# GPSDO_Supply.net
KiCad netlist of a schematic drawn in Altium Designer
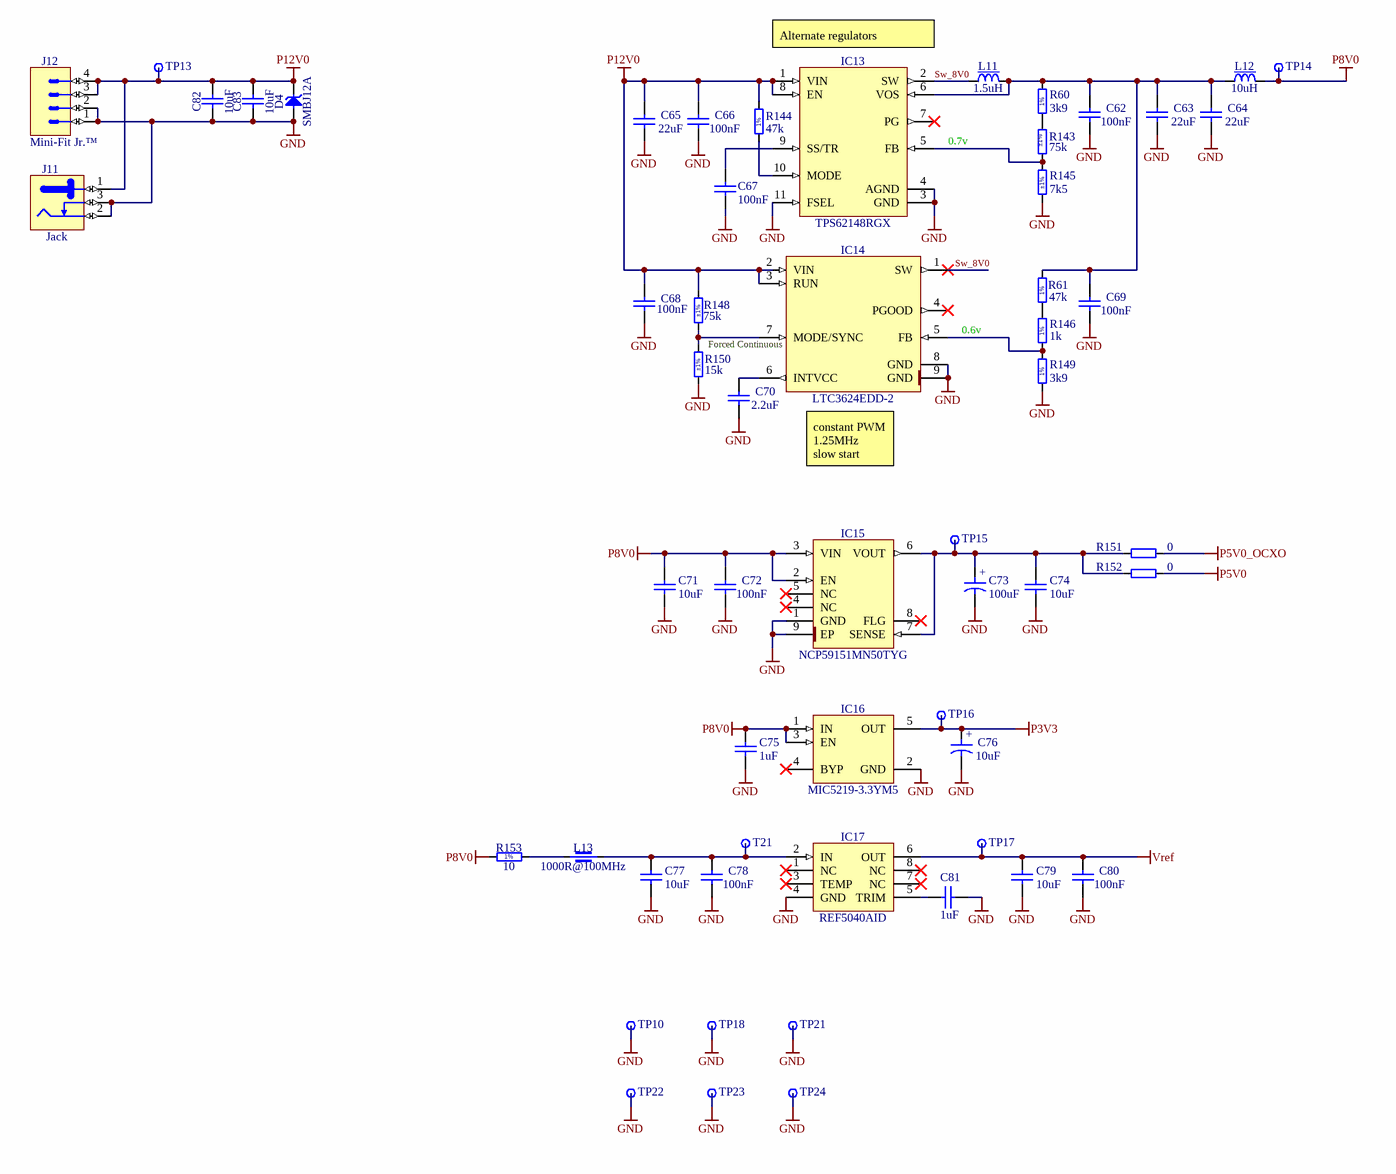
[diagram p0: GPSDO_Supply.SchDoc]

(export (version "E")
  (design (tool "Eeschema 10.0.6"))
  (components
    (comp (ref "C62")
      (value "100nF")
      (footprint "CAPC1005X55N")
      (description "Non-polarised capacitor")
      (fields
        (field (name "PART NUMBER") "CC0402_100NF_16V_10%_X5R")
        (field (name "VOLTAGE") "16V")
        (field (name "AUTHOR") "CERN DEM JLC")
      )
      (libsource (lib "Capacitors") (part "Capacitor - non polarized"))
    )
    (comp (ref "C63")
      (value "22uF")
      (footprint "CAPC2012X135N")
      (description "Non-polarised capacitor")
      (fields
        (field (name "PART NUMBER") "CC0805_22UF_16V_10%_X5R")
        (field (name "VOLTAGE") "16V")
        (field (name "AUTHOR") "CERN DEM JLC")
      )
      (libsource (lib "Capacitors") (part "Capacitor - non polarized"))
    )
    (comp (ref "C64")
      (value "22uF")
      (footprint "CAPC2012X135N")
      (description "Non-polarised capacitor")
      (fields
        (field (name "PART NUMBER") "CC0805_22UF_16V_10%_X5R")
        (field (name "VOLTAGE") "16V")
        (field (name "AUTHOR") "CERN DEM JLC")
      )
      (libsource (lib "Capacitors") (part "Capacitor - non polarized"))
    )
    (comp (ref "C65")
      (value "22uF")
      (footprint "CAPC2012X135N")
      (description "Non-polarised capacitor")
      (fields
        (field (name "PART NUMBER") "CC0805_22UF_16V_10%_X5R")
        (field (name "VOLTAGE") "16V")
        (field (name "AUTHOR") "CERN DEM JLC")
      )
      (libsource (lib "Capacitors") (part "Capacitor - non polarized"))
    )
    (comp (ref "C66")
      (value "100nF")
      (footprint "CAPC1005X55N")
      (description "Non-polarised capacitor")
      (fields
        (field (name "PART NUMBER") "CC0402_100NF_16V_10%_X5R")
        (field (name "VOLTAGE") "16V")
        (field (name "AUTHOR") "CERN DEM JLC")
      )
      (libsource (lib "Capacitors") (part "Capacitor - non polarized"))
    )
    (comp (ref "C67")
      (value "100nF")
      (footprint "CAPC1005X55N")
      (description "Non-polarised capacitor")
      (fields
        (field (name "PART NUMBER") "CC0402_100NF_16V_10%_X5R")
        (field (name "VOLTAGE") "16V")
        (field (name "AUTHOR") "CERN DEM JLC")
      )
      (libsource (lib "Capacitors") (part "Capacitor - non polarized"))
    )
    (comp (ref "C68")
      (value "100nF")
      (footprint "CAPC1005X55N")
      (description "Non-polarised capacitor")
      (fields
        (field (name "PART NUMBER") "CC0402_100NF_16V_10%_X5R")
        (field (name "VOLTAGE") "16V")
        (field (name "AUTHOR") "CERN DEM JLC")
      )
      (libsource (lib "Capacitors") (part "Capacitor - non polarized"))
    )
    (comp (ref "C69")
      (value "100nF")
      (footprint "CAPC1005X55N")
      (description "Non-polarised capacitor")
      (fields
        (field (name "PART NUMBER") "CC0402_100NF_16V_10%_X5R")
        (field (name "VOLTAGE") "16V")
        (field (name "AUTHOR") "CERN DEM JLC")
      )
      (libsource (lib "Capacitors") (part "Capacitor - non polarized"))
    )
    (comp (ref "C70")
      (value "2.2uF")
      (footprint "CAPC1005X55N")
      (description "Non-polarised capacitor")
      (fields
        (field (name "PART NUMBER") "CC0402_2.2UF_16V_10%_X5R")
        (field (name "VOLTAGE") "16V")
        (field (name "AUTHOR") "CERN DEM BC")
      )
      (libsource (lib "Capacitors") (part "Capacitor - non polarized"))
    )
    (comp (ref "C71")
      (value "10uF")
      (footprint "CAPC1608X80N")
      (description "Non-polarised capacitor")
      (fields
        (field (name "PART NUMBER") "CC0603_10UF_10V_10%_X5R")
        (field (name "VOLTAGE") "10V")
        (field (name "AUTHOR") "CERN DEM JLC")
      )
      (libsource (lib "Capacitors") (part "Capacitor - non polarized"))
    )
    (comp (ref "C72")
      (value "100nF")
      (footprint "CAPC1005X55N")
      (description "Non-polarised capacitor")
      (fields
        (field (name "PART NUMBER") "CC0402_100NF_16V_10%_X5R")
        (field (name "VOLTAGE") "16V")
        (field (name "AUTHOR") "CERN DEM JLC")
      )
      (libsource (lib "Capacitors") (part "Capacitor - non polarized"))
    )
    (comp (ref "C73")
      (value "100uF")
      (footprint "CAPMP7343X310N")
      (description "Polarised capacitor")
      (fields
        (field (name "PART NUMBER") "CTE7343-31_100UF_20V_10%")
        (field (name "VOLTAGE") "20V")
        (field (name "AUTHOR") "CERN DEM JLC")
      )
      (libsource (lib "Capacitors") (part "Capacitor - polarized"))
    )
    (comp (ref "C74")
      (value "10uF")
      (footprint "CAPC1608X80N")
      (description "Non-polarised capacitor")
      (fields
        (field (name "PART NUMBER") "CC0603_10UF_10V_10%_X5R")
        (field (name "VOLTAGE") "10V")
        (field (name "AUTHOR") "CERN DEM JLC")
      )
      (libsource (lib "Capacitors") (part "Capacitor - non polarized"))
    )
    (comp (ref "C75")
      (value "1uF")
      (footprint "CAPC1005X55N")
      (description "Non-polarised capacitor")
      (fields
        (field (name "PART NUMBER") "CC0402_1UF_16V_10%_X5R")
        (field (name "VOLTAGE") "16V")
        (field (name "AUTHOR") "CERN DEM JLC")
      )
      (libsource (lib "Capacitors") (part "Capacitor - non polarized"))
    )
    (comp (ref "C76")
      (value "10uF")
      (footprint "CAPMP3216X180N")
      (description "Polarised capacitor")
      (fields
        (field (name "PART NUMBER") "CTE3216-18_10UF_16V_20%_AVX_TCJ")
        (field (name "VOLTAGE") "16V")
        (field (name "AUTHOR") "CERN DEM JLC")
      )
      (libsource (lib "Capacitors") (part "Capacitor - polarized"))
    )
    (comp (ref "C77")
      (value "10uF")
      (footprint "CAPC1608X80N")
      (description "Non-polarised capacitor")
      (fields
        (field (name "PART NUMBER") "CC0603_10UF_10V_10%_X5R")
        (field (name "VOLTAGE") "10V")
        (field (name "AUTHOR") "CERN DEM JLC")
      )
      (libsource (lib "Capacitors") (part "Capacitor - non polarized"))
    )
    (comp (ref "C78")
      (value "100nF")
      (footprint "CAPC1005X55N")
      (description "Non-polarised capacitor")
      (fields
        (field (name "PART NUMBER") "CC0402_100NF_16V_10%_X5R")
        (field (name "VOLTAGE") "16V")
        (field (name "AUTHOR") "CERN DEM JLC")
      )
      (libsource (lib "Capacitors") (part "Capacitor - non polarized"))
    )
    (comp (ref "C79")
      (value "10uF")
      (footprint "CAPC1608X80N")
      (description "Non-polarised capacitor")
      (fields
        (field (name "PART NUMBER") "CC0603_10UF_10V_10%_X5R")
        (field (name "VOLTAGE") "10V")
        (field (name "AUTHOR") "CERN DEM JLC")
      )
      (libsource (lib "Capacitors") (part "Capacitor - non polarized"))
    )
    (comp (ref "C80")
      (value "100nF")
      (footprint "CAPC1005X55N")
      (description "Non-polarised capacitor")
      (fields
        (field (name "PART NUMBER") "CC0402_100NF_16V_10%_X5R")
        (field (name "VOLTAGE") "16V")
        (field (name "AUTHOR") "CERN DEM JLC")
      )
      (libsource (lib "Capacitors") (part "Capacitor - non polarized"))
    )
    (comp (ref "C81")
      (value "1uF")
      (footprint "CAPC1005X55N")
      (description "Non-polarised capacitor")
      (fields
        (field (name "PART NUMBER") "CC0402_1UF_16V_10%_X5R")
        (field (name "VOLTAGE") "16V")
        (field (name "AUTHOR") "CERN DEM JLC")
      )
      (libsource (lib "Capacitors") (part "Capacitor - non polarized"))
    )
    (comp (ref "C82")
      (value "10uF")
      (footprint "CAPC1608X80N")
      (description "Non-polarised capacitor")
      (fields
        (field (name "PART NUMBER") "CC0603_10UF_16V_20%_X5R")
        (field (name "VOLTAGE") "16V")
        (field (name "AUTHOR") "CERN DEM MR")
      )
      (libsource (lib "Capacitors") (part "Capacitor - non polarized"))
    )
    (comp (ref "C83")
      (value "10uF")
      (footprint "CAPC1608X80N")
      (description "Non-polarised capacitor")
      (fields
        (field (name "PART NUMBER") "CC0603_10UF_16V_20%_X5R")
        (field (name "VOLTAGE") "16V")
        (field (name "AUTHOR") "CERN DEM MR")
      )
      (libsource (lib "Capacitors") (part "Capacitor - non polarized"))
    )
    (comp (ref "D4")
      (value "SMBJ12A")
      (footprint "DIOM5336X265N")
      (description "Zener Diode")
      (fields
        (field (name "VOLTAGE") "12V")
        (field (name "POWER") "600W")
        (field (name "AUTHOR") "CERN DEM JLC")
      )
      (libsource (lib "ICs And Semiconductors") (part "Diode Zener"))
    )
    (comp (ref "IC13")
      (value "TPS62148RGX")
      (footprint "TEXAS_RGX0011A")
      (description "3V-17V 2A Step-Down Converter, High Accuracy, With DCS-Control")
      (fields (field (name "MANUFACTURER") "TEXAS INSTRUMENTS") (field (name "AUTHOR") "CERN DEM MR"))
      (libsource (lib "ICs And Semiconductors") (part "TPS62148"))
    )
    (comp (ref "IC14")
      (value "LTC3624EDD-2")
      (footprint "SON50P300X300X80-9N-R175X248")
      (description "Adjustable, 2A, Synchronous Step-Down Regulator with 3.5µA Quiescent Current")
      (fields (field (name "MANUFACTURER") "LINEAR TECHNOLOGY") (field (name "AUTHOR") "CERN DEM HF"))
      (libsource (lib "Regulators") (part "LTC3624 _DD"))
    )
    (comp (ref "IC15")
      (value "NCP59151MN50TYG")
      (footprint "SON80P400X400X100-9N-R221X239")
      (description "1.5 A, Very Low-Dropout (VLDO) Fast Transient Response Regulator")
      (fields (field (name "MANUFACTURER") "ON SEMICONDUCTOR") (field (name "AUTHOR") "CERN DEM JLC"))
      (libsource (lib "ICs And Semiconductors") (part "NCP59151MN"))
    )
    (comp (ref "IC16")
      (value "MIC5219-3.3YM5")
      (footprint "SOT95P280X145-5N")
      (description "500mA Peak Output LDO Regulator")
      (fields (field (name "MANUFACTURER") "MICROCHIP TECHNOLOGY") (field (name "AUTHOR") "CERN DEM WB"))
      (libsource (lib "ICs And Semiconductors") (part "MIC5219-X.XYM5"))
    )
    (comp (ref "IC17")
      (value "REF5040AID")
      (footprint "SOIC127P600X175-8N")
      (description "Low-Noise, Very Low Drift, Precision Voltage Reference")
      (fields (field (name "MANUFACTURER") "TEXAS INSTRUMENTS") (field (name "AUTHOR") "CERN DEM MR"))
      (libsource (lib "GPSDO") (part "REF5040AID"))
    )
    (comp (ref "J11")
      (value "Jack")
      (footprint "CUI_PJ-102BH")
      (description "2.5 mm Center Pin, 5A, 24V Right Angle, Through Hole, Tapered Pins, DC Power Jack Connector")
      (fields
        (field (name "PART NUMBER") "CUI_PJ-102BH")
        (field (name "MANUFACTURER") "CUI INC.")
        (field (name "AUTHOR") "CERN DEM JLC")
      )
      (libsource (lib "Connectors") (part "CUI_PJ-102BH"))
    )
    (comp (ref "J12")
      (value "Mini-Fit Jr.™")
      (footprint "MOLEX_39-30-0040")
      (description "Connector 4 Male")
      (fields
        (field (name "PART NUMBER") "MOLEX_39-30-0040")
        (field (name "MANUFACTURER") "MOLEX")
        (field (name "AUTHOR") "CERN DEM JLC")
      )
      (libsource (lib "Connectors") (part "Connector 4 Male"))
    )
    (comp (ref "L11")
      (value "1.5uH")
      (footprint "IND_TDK_SPM6530")
      (description "Inductor With Core")
      (fields
        (field (name "PART NUMBER") "IND_1.5UH_20%_TDK_SPM6530")
        (field (name "POWER") "11A")
        (field (name "AUTHOR") "CERN DEM MR")
      )
      (libsource (lib "Inductors & Transformers") (part "Inductor With Magnetic core"))
    )
    (comp (ref "L12")
      (value "10uH")
      (footprint "IND_MURATA-PS_8400")
      (description "Inductor With Core")
      (fields
        (field (name "PART NUMBER") "IND_10UH_10%_MURATA-PS_8400")
        (field (name "POWER") "950mA")
        (field (name "AUTHOR") "CERN DEM JLC")
      )
      (libsource (lib "Inductors & Transformers") (part "Inductor With Magnetic core"))
    )
    (comp (ref "L13")
      (value "1000R@100MHz")
      (footprint "INDC2012X145N")
      (fields
        (field (name "PART NUMBER") "IND0805_MURATA_BLM21AH1025N1D")
        (field (name "POWER") "600mA")
        (field (name "TOLERANCE") "±25%")
        (field (name "AUTHOR") "CERN DEM JLC")
      )
      (libsource (lib "GPSDO") (part "IND0805_MURATA_BLM21AH1025N1D"))
    )
    (comp (ref "R60")
      (value "3k9")
      (footprint "RESC1005X40N")
      (description "Resistor - 1%")
      (fields
        (field (name "PART NUMBER") "R0402_3K9_1%_0.0625W_100PPM")
        (field (name "POWER") "0.0625W")
        (field (name "AUTHOR") "CERN DEM JLC")
      )
      (libsource (lib "Resistors") (part "Resistor - 1%"))
    )
    (comp (ref "R61")
      (value "47k")
      (footprint "RESC1608X55N")
      (description "Resistor - 1%")
      (fields
        (field (name "PART NUMBER") "R0603_47K_1%_0.1W_100PPM")
        (field (name "POWER") "0.1W")
        (field (name "AUTHOR") "CERN DEM JLC")
      )
      (libsource (lib "Resistors") (part "Resistor - 1%"))
    )
    (comp (ref "R143")
      (value "75k")
      (footprint "RESC1608X55N")
      (description "Resistor - 1%")
      (fields
        (field (name "PART NUMBER") "R0603_75K_1%_0.1W_100PPM")
        (field (name "POWER") "0.1W")
        (field (name "TOLERANCE") "±1%")
        (field (name "AUTHOR") "CERN DEM JLC")
      )
      (libsource (lib "Resistors") (part "Resistor - 1%"))
    )
    (comp (ref "R144")
      (value "47k")
      (footprint "RESC1608X55N")
      (description "Resistor - 1%")
      (fields
        (field (name "PART NUMBER") "R0603_47K_1%_0.1W_100PPM")
        (field (name "POWER") "0.1W")
        (field (name "AUTHOR") "CERN DEM JLC")
      )
      (libsource (lib "Resistors") (part "Resistor - 1%"))
    )
    (comp (ref "R145")
      (value "7k5")
      (footprint "RESC1005X40N")
      (description "Resistor - 1%")
      (fields
        (field (name "TOLERANCE") "±1%")
        (field (name "PART NUMBER") "R0402_7K5_1%_0.0625W_100PPM")
        (field (name "POWER") "0.0625W")
        (field (name "AUTHOR") "CERN DEM JLC")
      )
      (libsource (lib "") (part "Resistor - 1%_1"))
    )
    (comp (ref "R146")
      (value "1k")
      (footprint "RESC1005X40N")
      (description "Resistor - 1%")
      (fields
        (field (name "PART NUMBER") "R0402_1K_1%_0.0625W_100PPM")
        (field (name "POWER") "0.0625W")
        (field (name "AUTHOR") "CERN DEM JLC")
      )
      (libsource (lib "Resistors") (part "Resistor - 1%"))
    )
    (comp (ref "R148")
      (value "75k")
      (footprint "RESC1005X40N")
      (description "Resistor - 1%")
      (fields
        (field (name "TOLERANCE") "±1%")
        (field (name "PART NUMBER") "R0402_75K_1%_0.0625W_100PPM")
        (field (name "POWER") "0.0625W")
        (field (name "AUTHOR") "CERN DEM JLC")
      )
      (libsource (lib "") (part "Resistor - 1%_1"))
    )
    (comp (ref "R149")
      (value "3k9")
      (footprint "RESC1005X40N")
      (description "Resistor - 1%")
      (fields
        (field (name "PART NUMBER") "R0402_3K9_1%_0.0625W_100PPM")
        (field (name "POWER") "0.0625W")
        (field (name "AUTHOR") "CERN DEM JLC")
      )
      (libsource (lib "Resistors") (part "Resistor - 1%"))
    )
    (comp (ref "R150")
      (value "15k")
      (footprint "RESC1005X40N")
      (description "Resistor - 1%")
      (fields
        (field (name "TOLERANCE") "±1%")
        (field (name "PART NUMBER") "R0402_15K_1%_0.0625W_100PPM")
        (field (name "POWER") "0.0625W")
        (field (name "AUTHOR") "CERN DEM JMW")
      )
      (libsource (lib "") (part "Resistor - 1%_1"))
    )
    (comp (ref "R151")
      (value "0")
      (footprint "RESC1005X40N")
      (description "Resistor")
      (fields
        (field (name "PART NUMBER") "R0402_0R_JUMPER")
        (field (name "MANUFACTURER") "GENERIC")
        (field (name "AUTHOR") "CERN DEM JLC")
      )
      (libsource (lib "Resistors") (part "Resistor"))
    )
    (comp (ref "R152")
      (value "0")
      (footprint "RESC1005X40N")
      (description "Resistor")
      (fields
        (field (name "PART NUMBER") "R0402_0R_JUMPER")
        (field (name "MANUFACTURER") "GENERIC")
        (field (name "AUTHOR") "CERN DEM JLC")
      )
      (libsource (lib "Resistors") (part "Resistor"))
    )
    (comp (ref "R153")
      (value "10")
      (footprint "RESC1005X40N")
      (description "Resistor - 1%")
      (fields
        (field (name "PART NUMBER") "R0402_10R_1%_0.0625W_200PPM")
        (field (name "POWER") "0.0625W")
        (field (name "AUTHOR") "CERN DEM JLC")
      )
      (libsource (lib "Resistors") (part "Resistor - 1%"))
    )
    (comp (ref "T21")
      (value "Test Point")
      (footprint "TPS127")
      (fields (field (name "PART NUMBER") "SMD_PAD_1.27X1.27MM") (field (name "AUTHOR") "CERN DEM JLC"))
      (libsource (lib "Eletro-mechanical") (part "Test Point"))
    )
    (comp (ref "TP10")
      (value "Test Point")
      (footprint "TPS127")
      (fields (field (name "PART NUMBER") "SMD_PAD_1.27X1.27MM") (field (name "AUTHOR") "CERN DEM JLC"))
      (libsource (lib "Eletro-mechanical") (part "Test Point"))
    )
    (comp (ref "TP13")
      (value "Test Point")
      (footprint "TPS127")
      (fields (field (name "PART NUMBER") "SMD_PAD_1.27X1.27MM") (field (name "AUTHOR") "CERN DEM JLC"))
      (libsource (lib "Eletro-mechanical") (part "Test Point"))
    )
    (comp (ref "TP14")
      (value "Test Point")
      (footprint "TPS127")
      (fields (field (name "PART NUMBER") "SMD_PAD_1.27X1.27MM") (field (name "AUTHOR") "CERN DEM JLC"))
      (libsource (lib "Eletro-mechanical") (part "Test Point"))
    )
    (comp (ref "TP15")
      (value "Test Point")
      (footprint "TPS127")
      (fields (field (name "PART NUMBER") "SMD_PAD_1.27X1.27MM") (field (name "AUTHOR") "CERN DEM JLC"))
      (libsource (lib "Eletro-mechanical") (part "Test Point"))
    )
    (comp (ref "TP16")
      (value "Test Point")
      (footprint "TPS127")
      (fields (field (name "PART NUMBER") "SMD_PAD_1.27X1.27MM") (field (name "AUTHOR") "CERN DEM JLC"))
      (libsource (lib "Eletro-mechanical") (part "Test Point"))
    )
    (comp (ref "TP17")
      (value "Test Point")
      (footprint "TPS127")
      (fields (field (name "PART NUMBER") "SMD_PAD_1.27X1.27MM") (field (name "AUTHOR") "CERN DEM JLC"))
      (libsource (lib "Eletro-mechanical") (part "Test Point"))
    )
    (comp (ref "TP18")
      (value "Test Point")
      (footprint "TPS127")
      (fields (field (name "PART NUMBER") "SMD_PAD_1.27X1.27MM") (field (name "AUTHOR") "CERN DEM JLC"))
      (libsource (lib "Eletro-mechanical") (part "Test Point"))
    )
    (comp (ref "TP21")
      (value "Test Point")
      (footprint "TPS127")
      (fields (field (name "PART NUMBER") "SMD_PAD_1.27X1.27MM") (field (name "AUTHOR") "CERN DEM JLC"))
      (libsource (lib "Eletro-mechanical") (part "Test Point"))
    )
    (comp (ref "TP22")
      (value "Test Point")
      (footprint "TPS127")
      (fields (field (name "PART NUMBER") "SMD_PAD_1.27X1.27MM") (field (name "AUTHOR") "CERN DEM JLC"))
      (libsource (lib "Eletro-mechanical") (part "Test Point"))
    )
    (comp (ref "TP23")
      (value "Test Point")
      (footprint "TPS127")
      (fields (field (name "PART NUMBER") "SMD_PAD_1.27X1.27MM") (field (name "AUTHOR") "CERN DEM JLC"))
      (libsource (lib "Eletro-mechanical") (part "Test Point"))
    )
    (comp (ref "TP24")
      (value "Test Point")
      (footprint "TPS127")
      (fields (field (name "PART NUMBER") "SMD_PAD_1.27X1.27MM") (field (name "AUTHOR") "CERN DEM JLC"))
      (libsource (lib "Eletro-mechanical") (part "Test Point"))
    )
  )
  (nets
    (net (code "1") (name "/Sw_8V0") (class "Default")
      (node (ref "IC13") (pin "2") (pinfunction "SW_2") (pintype "output"))
      (node (ref "IC14") (pin "1") (pinfunction "SW_1") (pintype "output"))
      (node (ref "L11") (pin "1") (pinfunction "1_1") (pintype "passive"))
    )
    (net (code "2") (name "GND") (class "Default")
      (node (ref "C62") (pin "1") (pinfunction "1_1") (pintype "passive"))
      (node (ref "C63") (pin "1") (pinfunction "1_1") (pintype "passive"))
      (node (ref "C64") (pin "1") (pinfunction "1_1") (pintype "passive"))
      (node (ref "C65") (pin "1") (pinfunction "1_1") (pintype "passive"))
      (node (ref "C66") (pin "1") (pinfunction "1_1") (pintype "passive"))
      (node (ref "C67") (pin "2") (pinfunction "2_2") (pintype "passive"))
      (node (ref "C68") (pin "1") (pinfunction "1_1") (pintype "passive"))
      (node (ref "C69") (pin "1") (pinfunction "1_1") (pintype "passive"))
      (node (ref "C70") (pin "1") (pinfunction "1_1") (pintype "passive"))
      (node (ref "C71") (pin "1") (pinfunction "1_1") (pintype "passive"))
      (node (ref "C72") (pin "1") (pinfunction "1_1") (pintype "passive"))
      (node (ref "C73") (pin "2") (pinfunction "2_2") (pintype "passive"))
      (node (ref "C74") (pin "1") (pinfunction "1_1") (pintype "passive"))
      (node (ref "C75") (pin "1") (pinfunction "1_1") (pintype "passive"))
      (node (ref "C76") (pin "2") (pinfunction "2_2") (pintype "passive"))
      (node (ref "C77") (pin "1") (pinfunction "1_1") (pintype "passive"))
      (node (ref "C78") (pin "1") (pinfunction "1_1") (pintype "passive"))
      (node (ref "C79") (pin "1") (pinfunction "1_1") (pintype "passive"))
      (node (ref "C80") (pin "1") (pinfunction "1_1") (pintype "passive"))
      (node (ref "C81") (pin "1") (pinfunction "1_1") (pintype "passive"))
      (node (ref "C82") (pin "1") (pinfunction "1_1") (pintype "passive"))
      (node (ref "C83") (pin "1") (pinfunction "1_1") (pintype "passive"))
      (node (ref "D4") (pin "2") (pinfunction "A_2") (pintype "passive"))
      (node (ref "IC13") (pin "11") (pinfunction "FSEL_11") (pintype "input"))
      (node (ref "IC13") (pin "3") (pinfunction "GND_3") (pintype "power_in"))
      (node (ref "IC13") (pin "4") (pinfunction "AGND_4") (pintype "power_in"))
      (node (ref "IC14") (pin "8") (pinfunction "GND_8") (pintype "power_in"))
      (node (ref "IC14") (pin "9") (pinfunction "GND_9") (pintype "power_in"))
      (node (ref "IC15") (pin "1") (pinfunction "GND_1") (pintype "power_in"))
      (node (ref "IC15") (pin "9") (pinfunction "EP_9") (pintype "power_in"))
      (node (ref "IC16") (pin "2") (pinfunction "GND_2") (pintype "power_in"))
      (node (ref "IC17") (pin "4") (pinfunction "GND_4") (pintype "power_in"))
      (node (ref "J11") (pin "2") (pinfunction "2_2") (pintype "bidirectional"))
      (node (ref "J11") (pin "3") (pinfunction "3_3") (pintype "bidirectional"))
      (node (ref "J12") (pin "1") (pinfunction "1_1") (pintype "bidirectional"))
      (node (ref "J12") (pin "2") (pinfunction "2_2") (pintype "bidirectional"))
      (node (ref "R145") (pin "1") (pinfunction "1_1") (pintype "passive"))
      (node (ref "R149") (pin "1") (pinfunction "1_1") (pintype "passive"))
      (node (ref "R150") (pin "1") (pinfunction "1_1") (pintype "passive"))
      (node (ref "TP10") (pin "1") (pinfunction "1_1") (pintype "bidirectional"))
      (node (ref "TP18") (pin "1") (pinfunction "1_1") (pintype "bidirectional"))
      (node (ref "TP21") (pin "1") (pinfunction "1_1") (pintype "bidirectional"))
      (node (ref "TP22") (pin "1") (pinfunction "1_1") (pintype "bidirectional"))
      (node (ref "TP23") (pin "1") (pinfunction "1_1") (pintype "bidirectional"))
      (node (ref "TP24") (pin "1") (pinfunction "1_1") (pintype "bidirectional"))
    )
    (net (code "3") (name "Net-(IC13-FB)") (class "Default")
      (node (ref "IC13") (pin "5") (pinfunction "FB_5") (pintype "input"))
      (node (ref "R143") (pin "1") (pinfunction "1_1") (pintype "passive"))
      (node (ref "R145") (pin "2") (pinfunction "2_2") (pintype "passive"))
    )
    (net (code "4") (name "Net-(IC13-MODE)") (class "Default")
      (node (ref "IC13") (pin "10") (pinfunction "MODE_10") (pintype "input"))
      (node (ref "R144") (pin "1") (pinfunction "1_1") (pintype "passive"))
    )
    (net (code "5") (name "Net-(IC13-SS{slash}TR)") (class "Default")
      (node (ref "C67") (pin "1") (pinfunction "1_1") (pintype "passive"))
      (node (ref "IC13") (pin "9") (pinfunction "SS/TR_9") (pintype "input"))
    )
    (net (code "6") (name "Net-(IC13-VOS)") (class "Default")
      (node (ref "C62") (pin "2") (pinfunction "2_2") (pintype "passive"))
      (node (ref "C63") (pin "2") (pinfunction "2_2") (pintype "passive"))
      (node (ref "C64") (pin "2") (pinfunction "2_2") (pintype "passive"))
      (node (ref "C69") (pin "2") (pinfunction "2_2") (pintype "passive"))
      (node (ref "IC13") (pin "6") (pinfunction "VOS_6") (pintype "input"))
      (node (ref "L11") (pin "2") (pinfunction "2_2") (pintype "passive"))
      (node (ref "L12") (pin "1") (pinfunction "1_1") (pintype "passive"))
      (node (ref "R60") (pin "2") (pinfunction "2_2") (pintype "passive"))
      (node (ref "R61") (pin "2") (pinfunction "2_2") (pintype "passive"))
    )
    (net (code "7") (name "Net-(IC14-FB)") (class "Default")
      (node (ref "IC14") (pin "5") (pinfunction "FB_5") (pintype "input"))
      (node (ref "R146") (pin "1") (pinfunction "1_1") (pintype "passive"))
      (node (ref "R149") (pin "2") (pinfunction "2_2") (pintype "passive"))
    )
    (net (code "8") (name "Net-(IC14-INTVCC)") (class "Default")
      (node (ref "C70") (pin "2") (pinfunction "2_2") (pintype "passive"))
      (node (ref "IC14") (pin "6") (pinfunction "INTVCC_6") (pintype "output"))
    )
    (net (code "9") (name "Net-(IC14-MODE{slash}SYNC)") (class "Default")
      (node (ref "IC14") (pin "7") (pinfunction "MODE/SYNC_7") (pintype "input"))
      (node (ref "R148") (pin "1") (pinfunction "1_1") (pintype "passive"))
      (node (ref "R150") (pin "2") (pinfunction "2_2") (pintype "passive"))
    )
    (net (code "10") (name "Net-(IC15-SENSE)") (class "Default")
      (node (ref "C73") (pin "1") (pinfunction "1_1") (pintype "passive"))
      (node (ref "C74") (pin "2") (pinfunction "2_2") (pintype "passive"))
      (node (ref "IC15") (pin "6") (pinfunction "VOUT_6") (pintype "output"))
      (node (ref "IC15") (pin "7") (pinfunction "SENSE_7") (pintype "input"))
      (node (ref "R151") (pin "1") (pinfunction "1_1") (pintype "passive"))
      (node (ref "R152") (pin "1") (pinfunction "1_1") (pintype "passive"))
      (node (ref "TP15") (pin "1") (pinfunction "1_1") (pintype "bidirectional"))
    )
    (net (code "11") (name "Net-(IC17-IN)") (class "Default")
      (node (ref "C77") (pin "2") (pinfunction "2_2") (pintype "passive"))
      (node (ref "C78") (pin "2") (pinfunction "2_2") (pintype "passive"))
      (node (ref "IC17") (pin "2") (pinfunction "IN_2") (pintype "input"))
      (node (ref "L13") (pin "2") (pinfunction "2_2") (pintype "passive"))
      (node (ref "T21") (pin "1") (pinfunction "1_1") (pintype "bidirectional"))
    )
    (net (code "12") (name "Net-(IC17-TRIM)") (class "Default")
      (node (ref "C81") (pin "2") (pinfunction "2_2") (pintype "passive"))
      (node (ref "IC17") (pin "5") (pinfunction "TRIM_5") (pintype "passive"))
    )
    (net (code "13") (name "Net-(L13-Pad1)") (class "Default")
      (node (ref "L13") (pin "1") (pinfunction "1_1") (pintype "passive"))
      (node (ref "R153") (pin "2") (pinfunction "2_2") (pintype "passive"))
    )
    (net (code "14") (name "Net-(R143-Pad2)") (class "Default")
      (node (ref "R143") (pin "2") (pinfunction "2_2") (pintype "passive"))
      (node (ref "R60") (pin "1") (pinfunction "1_1") (pintype "passive"))
    )
    (net (code "15") (name "Net-(R146-Pad2)") (class "Default")
      (node (ref "R146") (pin "2") (pinfunction "2_2") (pintype "passive"))
      (node (ref "R61") (pin "1") (pinfunction "1_1") (pintype "passive"))
    )
    (net (code "16") (name "P3V3") (class "Default")
      (node (ref "C76") (pin "1") (pinfunction "1_1") (pintype "passive"))
      (node (ref "IC16") (pin "5") (pinfunction "OUT_5") (pintype "power_in"))
      (node (ref "TP16") (pin "1") (pinfunction "1_1") (pintype "bidirectional"))
    )
    (net (code "17") (name "P5V0") (class "Default")
      (node (ref "R152") (pin "2") (pinfunction "2_2") (pintype "passive"))
    )
    (net (code "18") (name "P5V0_OCXO") (class "Default")
      (node (ref "R151") (pin "2") (pinfunction "2_2") (pintype "passive"))
    )
    (net (code "19") (name "P8V0") (class "Default")
      (node (ref "C71") (pin "2") (pinfunction "2_2") (pintype "passive"))
      (node (ref "C72") (pin "2") (pinfunction "2_2") (pintype "passive"))
      (node (ref "C75") (pin "2") (pinfunction "2_2") (pintype "passive"))
      (node (ref "IC15") (pin "2") (pinfunction "EN_2") (pintype "input"))
      (node (ref "IC15") (pin "3") (pinfunction "VIN_3") (pintype "input"))
      (node (ref "IC16") (pin "1") (pinfunction "IN_1") (pintype "input"))
      (node (ref "IC16") (pin "3") (pinfunction "EN_3") (pintype "input"))
      (node (ref "L12") (pin "2") (pinfunction "2_2") (pintype "passive"))
      (node (ref "R153") (pin "1") (pinfunction "1_1") (pintype "passive"))
      (node (ref "TP14") (pin "1") (pinfunction "1_1") (pintype "bidirectional"))
    )
    (net (code "20") (name "P12V0") (class "Default")
      (node (ref "C65") (pin "2") (pinfunction "2_2") (pintype "passive"))
      (node (ref "C66") (pin "2") (pinfunction "2_2") (pintype "passive"))
      (node (ref "C68") (pin "2") (pinfunction "2_2") (pintype "passive"))
      (node (ref "C82") (pin "2") (pinfunction "2_2") (pintype "passive"))
      (node (ref "C83") (pin "2") (pinfunction "2_2") (pintype "passive"))
      (node (ref "D4") (pin "1") (pinfunction "C_1") (pintype "passive"))
      (node (ref "IC13") (pin "1") (pinfunction "VIN_1") (pintype "input"))
      (node (ref "IC13") (pin "8") (pinfunction "EN_8") (pintype "input"))
      (node (ref "IC14") (pin "2") (pinfunction "VIN_2") (pintype "input"))
      (node (ref "IC14") (pin "3") (pinfunction "RUN_3") (pintype "input"))
      (node (ref "J11") (pin "1") (pinfunction "1_1") (pintype "bidirectional"))
      (node (ref "J12") (pin "3") (pinfunction "3_3") (pintype "bidirectional"))
      (node (ref "J12") (pin "4") (pinfunction "4_4") (pintype "bidirectional"))
      (node (ref "R144") (pin "2") (pinfunction "2_2") (pintype "passive"))
      (node (ref "R148") (pin "2") (pinfunction "2_2") (pintype "passive"))
      (node (ref "TP13") (pin "1") (pinfunction "1_1") (pintype "bidirectional"))
    )
    (net (code "21") (name "Vref") (class "Default")
      (node (ref "C79") (pin "2") (pinfunction "2_2") (pintype "passive"))
      (node (ref "C80") (pin "2") (pinfunction "2_2") (pintype "passive"))
      (node (ref "IC17") (pin "6") (pinfunction "OUT_6") (pintype "power_in"))
      (node (ref "TP17") (pin "1") (pinfunction "1_1") (pintype "bidirectional"))
    )
    (net (code "22") (name "unconnected-(IC13-PG-Pad7)") (class "Default")
      (node (ref "IC13") (pin "7") (pinfunction "PG_7") (pintype "output+no_connect"))
    )
    (net (code "23") (name "unconnected-(IC14-PGOOD-Pad4)") (class "Default")
      (node (ref "IC14") (pin "4") (pinfunction "PGOOD_4") (pintype "output+no_connect"))
    )
    (net (code "24") (name "unconnected-(IC15-FLG-Pad8)") (class "Default")
      (node (ref "IC15") (pin "8") (pinfunction "FLG_8") (pintype "open_collector+no_connect"))
    )
    (net (code "25") (name "unconnected-(IC15-NC-Pad4)") (class "Default")
      (node (ref "IC15") (pin "4") (pinfunction "NC_4") (pintype "passive+no_connect"))
    )
    (net (code "26") (name "unconnected-(IC15-NC-Pad5)") (class "Default")
      (node (ref "IC15") (pin "5") (pinfunction "NC_5") (pintype "passive+no_connect"))
    )
    (net (code "27") (name "unconnected-(IC16-BYP-Pad4)") (class "Default")
      (node (ref "IC16") (pin "4") (pinfunction "BYP_4") (pintype "passive+no_connect"))
    )
    (net (code "28") (name "unconnected-(IC17-NC-Pad1)") (class "Default")
      (node (ref "IC17") (pin "1") (pinfunction "NC_1") (pintype "passive+no_connect"))
    )
    (net (code "29") (name "unconnected-(IC17-NC-Pad7)") (class "Default")
      (node (ref "IC17") (pin "7") (pinfunction "NC_7") (pintype "passive+no_connect"))
    )
    (net (code "30") (name "unconnected-(IC17-NC-Pad8)") (class "Default")
      (node (ref "IC17") (pin "8") (pinfunction "NC_8") (pintype "passive+no_connect"))
    )
    (net (code "31") (name "unconnected-(IC17-TEMP-Pad3)") (class "Default")
      (node (ref "IC17") (pin "3") (pinfunction "TEMP_3") (pintype "passive+no_connect"))
    )
  )
)
